# ZynqPL_DDR.net
KiCad netlist of a schematic drawn in Altium Designer
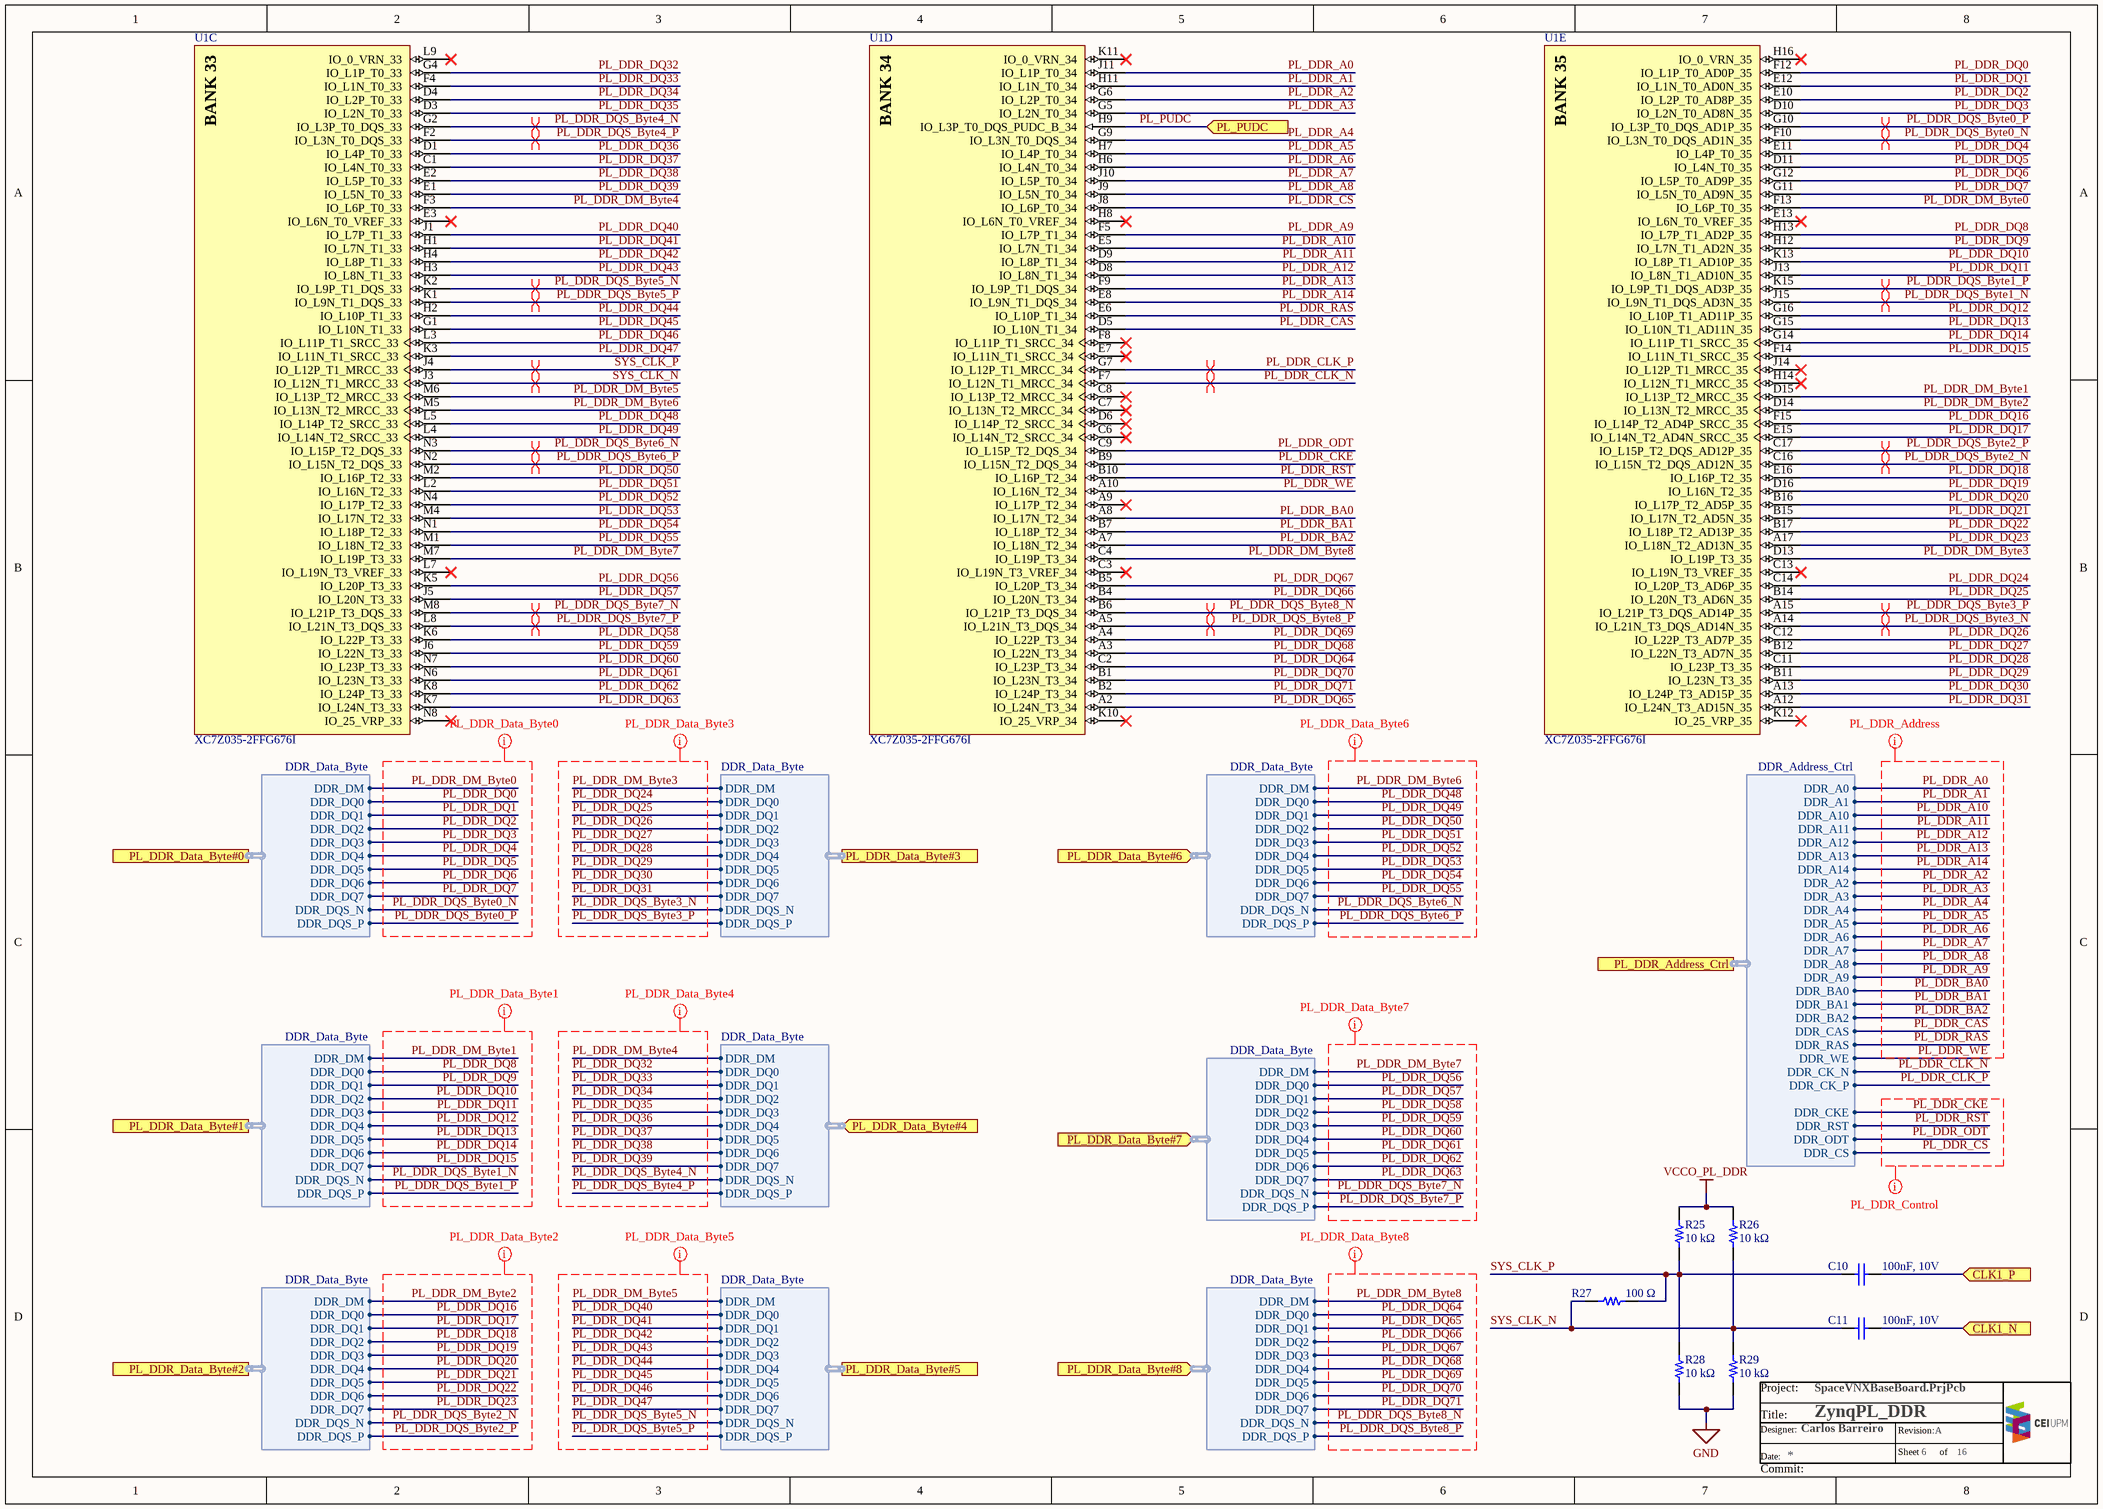
[diagram p0: ZynqPL_DDR.SchDoc]

(export (version "E")
  (design (tool "Eeschema 10.0.6"))
  (components
    (comp (ref "C10")
      (value "100nF, 10V")
      (footprint "WURTH_WCAP-CSGP_0402")
      (description "WCAP-CSGP Multilayer Ceramic Chip Capacitor, General Purpose, size 0402, X7R, 100nF, 10V")
      (fields
        (field (name "MANUFACTURER PART NUMBER") "885012205018")
        (field (name "MANUFACTURER") "Wurth Elektronik")
      )
      (libsource (lib "SpaceVNX") (part "885012205018"))
    )
    (comp (ref "C11")
      (value "100nF, 10V")
      (footprint "WURTH_WCAP-CSGP_0402")
      (description "WCAP-CSGP Multilayer Ceramic Chip Capacitor, General Purpose, size 0402, X7R, 100nF, 10V")
      (fields
        (field (name "MANUFACTURER PART NUMBER") "885012205018")
        (field (name "MANUFACTURER") "Wurth Elektronik")
      )
      (libsource (lib "SpaceVNX") (part "885012205018"))
    )
    (comp (ref "R25")
      (value "10 kΩ")
      (footprint "PANASONIC_ERJ2G_0402")
      (description "General Purpose Thick Film Chip Resistors")
      (fields (field (name "MANUFACTURER") "Panasonic"))
      (libsource (lib "SpaceVNX") (part "ERJ2RKF1002X"))
    )
    (comp (ref "R26")
      (value "10 kΩ")
      (footprint "PANASONIC_ERJ2G_0402")
      (description "General Purpose Thick Film Chip Resistors")
      (fields (field (name "MANUFACTURER") "Panasonic"))
      (libsource (lib "SpaceVNX") (part "ERJ2RKF1002X"))
    )
    (comp (ref "R27")
      (value "100 Ω")
      (footprint "PANASONIC_ERJ2G_0402")
      (description "General Purpose Thick Film Chip Resistors")
      (fields (field (name "MANUFACTURER") "Panasonic"))
      (libsource (lib "SpaceVNX") (part "ERJ2GEJ101X"))
    )
    (comp (ref "R28")
      (value "10 kΩ")
      (footprint "PANASONIC_ERJ2G_0402")
      (description "General Purpose Thick Film Chip Resistors")
      (fields (field (name "MANUFACTURER") "Panasonic"))
      (libsource (lib "SpaceVNX") (part "ERJ2RKF1002X"))
    )
    (comp (ref "R29")
      (value "10 kΩ")
      (footprint "PANASONIC_ERJ2G_0402")
      (description "General Purpose Thick Film Chip Resistors")
      (fields (field (name "MANUFACTURER") "Panasonic"))
      (libsource (lib "SpaceVNX") (part "ERJ2RKF1002X"))
    )
    (comp (ref "U1")
      (value "XC7Z035-2FFG676I")
      (footprint "XILINX_FBG676")
      (fields (field (name "PARTNUMBER") "XC7Z035-2FBG676I") (field (name "GENERIC PART NUMBER") "XC7Z035"))
      (libsource (lib "SpaceVNX") (part "XC7Z035-2FFG676I"))
    )
  )
  (nets
    (net (code "3") (name "/CLK1_N") (class "Default")
      (node (ref "C11") (pin "2") (pinfunction "2_2") (pintype "passive"))
    )
    (net (code "4") (name "/CLK1_P") (class "Default")
      (node (ref "C10") (pin "2") (pinfunction "2_2") (pintype "passive"))
    )
    (net (code "5") (name "/PL_DDR_A0") (class "Default")
      (node (ref "U1") (pin "J11") (pinfunction "IO_L1P_T0_34_J11") (pintype "bidirectional"))
    )
    (net (code "6") (name "/PL_DDR_A1") (class "Default")
      (node (ref "U1") (pin "H11") (pinfunction "IO_L1N_T0_34_H11") (pintype "bidirectional"))
    )
    (net (code "7") (name "/PL_DDR_A2") (class "Default")
      (node (ref "U1") (pin "G6") (pinfunction "IO_L2P_T0_34_G6") (pintype "bidirectional"))
    )
    (net (code "8") (name "/PL_DDR_A3") (class "Default")
      (node (ref "U1") (pin "G5") (pinfunction "IO_L2N_T0_34_G5") (pintype "bidirectional"))
    )
    (net (code "9") (name "/PL_DDR_A4") (class "Default")
      (node (ref "U1") (pin "G9") (pinfunction "IO_L3N_T0_DQS_34_G9") (pintype "bidirectional"))
    )
    (net (code "10") (name "/PL_DDR_A5") (class "Default")
      (node (ref "U1") (pin "H7") (pinfunction "IO_L4P_T0_34_H7") (pintype "bidirectional"))
    )
    (net (code "11") (name "/PL_DDR_A6") (class "Default")
      (node (ref "U1") (pin "H6") (pinfunction "IO_L4N_T0_34_H6") (pintype "bidirectional"))
    )
    (net (code "12") (name "/PL_DDR_A7") (class "Default")
      (node (ref "U1") (pin "J10") (pinfunction "IO_L5P_T0_34_J10") (pintype "bidirectional"))
    )
    (net (code "13") (name "/PL_DDR_A8") (class "Default")
      (node (ref "U1") (pin "J9") (pinfunction "IO_L5N_T0_34_J9") (pintype "bidirectional"))
    )
    (net (code "14") (name "/PL_DDR_A9") (class "Default")
      (node (ref "U1") (pin "F5") (pinfunction "IO_L7P_T1_34_F5") (pintype "bidirectional"))
    )
    (net (code "15") (name "/PL_DDR_A10") (class "Default")
      (node (ref "U1") (pin "E5") (pinfunction "IO_L7N_T1_34_E5") (pintype "bidirectional"))
    )
    (net (code "16") (name "/PL_DDR_A11") (class "Default")
      (node (ref "U1") (pin "D9") (pinfunction "IO_L8P_T1_34_D9") (pintype "bidirectional"))
    )
    (net (code "17") (name "/PL_DDR_A12") (class "Default")
      (node (ref "U1") (pin "D8") (pinfunction "IO_L8N_T1_34_D8") (pintype "bidirectional"))
    )
    (net (code "18") (name "/PL_DDR_A13") (class "Default")
      (node (ref "U1") (pin "F9") (pinfunction "IO_L9P_T1_DQS_34_F9") (pintype "bidirectional"))
    )
    (net (code "19") (name "/PL_DDR_A14") (class "Default")
      (node (ref "U1") (pin "E8") (pinfunction "IO_L9N_T1_DQS_34_E8") (pintype "bidirectional"))
    )
    (net (code "20") (name "/PL_DDR_BA0") (class "Default")
      (node (ref "U1") (pin "A8") (pinfunction "IO_L17N_T2_34_A8") (pintype "bidirectional"))
    )
    (net (code "21") (name "/PL_DDR_BA1") (class "Default")
      (node (ref "U1") (pin "B7") (pinfunction "IO_L18P_T2_34_B7") (pintype "bidirectional"))
    )
    (net (code "22") (name "/PL_DDR_BA2") (class "Default")
      (node (ref "U1") (pin "A7") (pinfunction "IO_L18N_T2_34_A7") (pintype "bidirectional"))
    )
    (net (code "23") (name "/PL_DDR_CAS") (class "Default")
      (node (ref "U1") (pin "D5") (pinfunction "IO_L10N_T1_34_D5") (pintype "bidirectional"))
    )
    (net (code "24") (name "/PL_DDR_CKE") (class "Default")
      (node (ref "U1") (pin "B9") (pinfunction "IO_L15N_T2_DQS_34_B9") (pintype "bidirectional"))
    )
    (net (code "25") (name "/PL_DDR_CLK_N") (class "Default")
      (node (ref "U1") (pin "F7") (pinfunction "IO_L12N_T1_MRCC_34_F7") (pintype "bidirectional"))
    )
    (net (code "26") (name "/PL_DDR_CLK_P") (class "Default")
      (node (ref "U1") (pin "G7") (pinfunction "IO_L12P_T1_MRCC_34_G7") (pintype "bidirectional"))
    )
    (net (code "27") (name "/PL_DDR_CS") (class "Default")
      (node (ref "U1") (pin "J8") (pinfunction "IO_L6P_T0_34_J8") (pintype "bidirectional"))
    )
    (net (code "28") (name "/PL_DDR_DM_Byte0") (class "Default")
      (node (ref "U1") (pin "F13") (pinfunction "IO_L6P_T0_35_F13") (pintype "bidirectional"))
    )
    (net (code "29") (name "/PL_DDR_DM_Byte1") (class "Default")
      (node (ref "U1") (pin "D15") (pinfunction "IO_L13P_T2_MRCC_35_D15") (pintype "bidirectional"))
    )
    (net (code "30") (name "/PL_DDR_DM_Byte2") (class "Default")
      (node (ref "U1") (pin "D14") (pinfunction "IO_L13N_T2_MRCC_35_D14") (pintype "bidirectional"))
    )
    (net (code "31") (name "/PL_DDR_DM_Byte3") (class "Default")
      (node (ref "U1") (pin "D13") (pinfunction "IO_L19P_T3_35_D13") (pintype "bidirectional"))
    )
    (net (code "32") (name "/PL_DDR_DM_Byte4") (class "Default")
      (node (ref "U1") (pin "F3") (pinfunction "IO_L6P_T0_33_F3") (pintype "bidirectional"))
    )
    (net (code "33") (name "/PL_DDR_DM_Byte5") (class "Default")
      (node (ref "U1") (pin "M6") (pinfunction "IO_L13P_T2_MRCC_33_M6") (pintype "bidirectional"))
    )
    (net (code "34") (name "/PL_DDR_DM_Byte6") (class "Default")
      (node (ref "U1") (pin "M5") (pinfunction "IO_L13N_T2_MRCC_33_M5") (pintype "bidirectional"))
    )
    (net (code "35") (name "/PL_DDR_DM_Byte7") (class "Default")
      (node (ref "U1") (pin "M7") (pinfunction "IO_L19P_T3_33_M7") (pintype "bidirectional"))
    )
    (net (code "36") (name "/PL_DDR_DM_Byte8") (class "Default")
      (node (ref "U1") (pin "C4") (pinfunction "IO_L19P_T3_34_C4") (pintype "bidirectional"))
    )
    (net (code "37") (name "/PL_DDR_DQ0") (class "Default")
      (node (ref "U1") (pin "F12") (pinfunction "IO_L1P_T0_AD0P_35_F12") (pintype "bidirectional"))
    )
    (net (code "38") (name "/PL_DDR_DQ1") (class "Default")
      (node (ref "U1") (pin "E12") (pinfunction "IO_L1N_T0_AD0N_35_E12") (pintype "bidirectional"))
    )
    (net (code "39") (name "/PL_DDR_DQ2") (class "Default")
      (node (ref "U1") (pin "E10") (pinfunction "IO_L2P_T0_AD8P_35_E10") (pintype "bidirectional"))
    )
    (net (code "40") (name "/PL_DDR_DQ3") (class "Default")
      (node (ref "U1") (pin "D10") (pinfunction "IO_L2N_T0_AD8N_35_D10") (pintype "bidirectional"))
    )
    (net (code "41") (name "/PL_DDR_DQ4") (class "Default")
      (node (ref "U1") (pin "E11") (pinfunction "IO_L4P_T0_35_E11") (pintype "bidirectional"))
    )
    (net (code "42") (name "/PL_DDR_DQ5") (class "Default")
      (node (ref "U1") (pin "D11") (pinfunction "IO_L4N_T0_35_D11") (pintype "bidirectional"))
    )
    (net (code "43") (name "/PL_DDR_DQ6") (class "Default")
      (node (ref "U1") (pin "G12") (pinfunction "IO_L5P_T0_AD9P_35_G12") (pintype "bidirectional"))
    )
    (net (code "44") (name "/PL_DDR_DQ7") (class "Default")
      (node (ref "U1") (pin "G11") (pinfunction "IO_L5N_T0_AD9N_35_G11") (pintype "bidirectional"))
    )
    (net (code "45") (name "/PL_DDR_DQ8") (class "Default")
      (node (ref "U1") (pin "H13") (pinfunction "IO_L7P_T1_AD2P_35_H13") (pintype "bidirectional"))
    )
    (net (code "46") (name "/PL_DDR_DQ9") (class "Default")
      (node (ref "U1") (pin "H12") (pinfunction "IO_L7N_T1_AD2N_35_H12") (pintype "bidirectional"))
    )
    (net (code "47") (name "/PL_DDR_DQ10") (class "Default")
      (node (ref "U1") (pin "K13") (pinfunction "IO_L8P_T1_AD10P_35_K13") (pintype "bidirectional"))
    )
    (net (code "48") (name "/PL_DDR_DQ11") (class "Default")
      (node (ref "U1") (pin "J13") (pinfunction "IO_L8N_T1_AD10N_35_J13") (pintype "bidirectional"))
    )
    (net (code "49") (name "/PL_DDR_DQ12") (class "Default")
      (node (ref "U1") (pin "G16") (pinfunction "IO_L10P_T1_AD11P_35_G16") (pintype "bidirectional"))
    )
    (net (code "50") (name "/PL_DDR_DQ13") (class "Default")
      (node (ref "U1") (pin "G15") (pinfunction "IO_L10N_T1_AD11N_35_G15") (pintype "bidirectional"))
    )
    (net (code "51") (name "/PL_DDR_DQ14") (class "Default")
      (node (ref "U1") (pin "G14") (pinfunction "IO_L11P_T1_SRCC_35_G14") (pintype "bidirectional"))
    )
    (net (code "52") (name "/PL_DDR_DQ15") (class "Default")
      (node (ref "U1") (pin "F14") (pinfunction "IO_L11N_T1_SRCC_35_F14") (pintype "bidirectional"))
    )
    (net (code "53") (name "/PL_DDR_DQ16") (class "Default")
      (node (ref "U1") (pin "F15") (pinfunction "IO_L14P_T2_AD4P_SRCC_35_F15") (pintype "bidirectional"))
    )
    (net (code "54") (name "/PL_DDR_DQ17") (class "Default")
      (node (ref "U1") (pin "E15") (pinfunction "IO_L14N_T2_AD4N_SRCC_35_E15") (pintype "bidirectional"))
    )
    (net (code "55") (name "/PL_DDR_DQ18") (class "Default")
      (node (ref "U1") (pin "E16") (pinfunction "IO_L16P_T2_35_E16") (pintype "bidirectional"))
    )
    (net (code "56") (name "/PL_DDR_DQ19") (class "Default")
      (node (ref "U1") (pin "D16") (pinfunction "IO_L16N_T2_35_D16") (pintype "bidirectional"))
    )
    (net (code "57") (name "/PL_DDR_DQ20") (class "Default")
      (node (ref "U1") (pin "B16") (pinfunction "IO_L17P_T2_AD5P_35_B16") (pintype "bidirectional"))
    )
    (net (code "58") (name "/PL_DDR_DQ21") (class "Default")
      (node (ref "U1") (pin "B15") (pinfunction "IO_L17N_T2_AD5N_35_B15") (pintype "bidirectional"))
    )
    (net (code "59") (name "/PL_DDR_DQ22") (class "Default")
      (node (ref "U1") (pin "B17") (pinfunction "IO_L18P_T2_AD13P_35_B17") (pintype "bidirectional"))
    )
    (net (code "60") (name "/PL_DDR_DQ23") (class "Default")
      (node (ref "U1") (pin "A17") (pinfunction "IO_L18N_T2_AD13N_35_A17") (pintype "bidirectional"))
    )
    (net (code "61") (name "/PL_DDR_DQ24") (class "Default")
      (node (ref "U1") (pin "C14") (pinfunction "IO_L20P_T3_AD6P_35_C14") (pintype "bidirectional"))
    )
    (net (code "62") (name "/PL_DDR_DQ25") (class "Default")
      (node (ref "U1") (pin "B14") (pinfunction "IO_L20N_T3_AD6N_35_B14") (pintype "bidirectional"))
    )
    (net (code "63") (name "/PL_DDR_DQ26") (class "Default")
      (node (ref "U1") (pin "C12") (pinfunction "IO_L22P_T3_AD7P_35_C12") (pintype "bidirectional"))
    )
    (net (code "64") (name "/PL_DDR_DQ27") (class "Default")
      (node (ref "U1") (pin "B12") (pinfunction "IO_L22N_T3_AD7N_35_B12") (pintype "bidirectional"))
    )
    (net (code "65") (name "/PL_DDR_DQ28") (class "Default")
      (node (ref "U1") (pin "C11") (pinfunction "IO_L23P_T3_35_C11") (pintype "bidirectional"))
    )
    (net (code "66") (name "/PL_DDR_DQ29") (class "Default")
      (node (ref "U1") (pin "B11") (pinfunction "IO_L23N_T3_35_B11") (pintype "bidirectional"))
    )
    (net (code "67") (name "/PL_DDR_DQ30") (class "Default")
      (node (ref "U1") (pin "A13") (pinfunction "IO_L24P_T3_AD15P_35_A13") (pintype "bidirectional"))
    )
    (net (code "68") (name "/PL_DDR_DQ31") (class "Default")
      (node (ref "U1") (pin "A12") (pinfunction "IO_L24N_T3_AD15N_35_A12") (pintype "bidirectional"))
    )
    (net (code "69") (name "/PL_DDR_DQ32") (class "Default")
      (node (ref "U1") (pin "G4") (pinfunction "IO_L1P_T0_33_G4") (pintype "bidirectional"))
    )
    (net (code "70") (name "/PL_DDR_DQ33") (class "Default")
      (node (ref "U1") (pin "F4") (pinfunction "IO_L1N_T0_33_F4") (pintype "bidirectional"))
    )
    (net (code "71") (name "/PL_DDR_DQ34") (class "Default")
      (node (ref "U1") (pin "D4") (pinfunction "IO_L2P_T0_33_D4") (pintype "bidirectional"))
    )
    (net (code "72") (name "/PL_DDR_DQ35") (class "Default")
      (node (ref "U1") (pin "D3") (pinfunction "IO_L2N_T0_33_D3") (pintype "bidirectional"))
    )
    (net (code "73") (name "/PL_DDR_DQ36") (class "Default")
      (node (ref "U1") (pin "D1") (pinfunction "IO_L4P_T0_33_D1") (pintype "bidirectional"))
    )
    (net (code "74") (name "/PL_DDR_DQ37") (class "Default")
      (node (ref "U1") (pin "C1") (pinfunction "IO_L4N_T0_33_C1") (pintype "bidirectional"))
    )
    (net (code "75") (name "/PL_DDR_DQ38") (class "Default")
      (node (ref "U1") (pin "E2") (pinfunction "IO_L5P_T0_33_E2") (pintype "bidirectional"))
    )
    (net (code "76") (name "/PL_DDR_DQ39") (class "Default")
      (node (ref "U1") (pin "E1") (pinfunction "IO_L5N_T0_33_E1") (pintype "bidirectional"))
    )
    (net (code "77") (name "/PL_DDR_DQ40") (class "Default")
      (node (ref "U1") (pin "J1") (pinfunction "IO_L7P_T1_33_J1") (pintype "bidirectional"))
    )
    (net (code "78") (name "/PL_DDR_DQ41") (class "Default")
      (node (ref "U1") (pin "H1") (pinfunction "IO_L7N_T1_33_H1") (pintype "bidirectional"))
    )
    (net (code "79") (name "/PL_DDR_DQ42") (class "Default")
      (node (ref "U1") (pin "H4") (pinfunction "IO_L8P_T1_33_H4") (pintype "bidirectional"))
    )
    (net (code "80") (name "/PL_DDR_DQ43") (class "Default")
      (node (ref "U1") (pin "H3") (pinfunction "IO_L8N_T1_33_H3") (pintype "bidirectional"))
    )
    (net (code "81") (name "/PL_DDR_DQ44") (class "Default")
      (node (ref "U1") (pin "H2") (pinfunction "IO_L10P_T1_33_H2") (pintype "bidirectional"))
    )
    (net (code "82") (name "/PL_DDR_DQ45") (class "Default")
      (node (ref "U1") (pin "G1") (pinfunction "IO_L10N_T1_33_G1") (pintype "bidirectional"))
    )
    (net (code "83") (name "/PL_DDR_DQ46") (class "Default")
      (node (ref "U1") (pin "L3") (pinfunction "IO_L11P_T1_SRCC_33_L3") (pintype "bidirectional"))
    )
    (net (code "84") (name "/PL_DDR_DQ47") (class "Default")
      (node (ref "U1") (pin "K3") (pinfunction "IO_L11N_T1_SRCC_33_K3") (pintype "bidirectional"))
    )
    (net (code "85") (name "/PL_DDR_DQ48") (class "Default")
      (node (ref "U1") (pin "L5") (pinfunction "IO_L14P_T2_SRCC_33_L5") (pintype "bidirectional"))
    )
    (net (code "86") (name "/PL_DDR_DQ49") (class "Default")
      (node (ref "U1") (pin "L4") (pinfunction "IO_L14N_T2_SRCC_33_L4") (pintype "bidirectional"))
    )
    (net (code "87") (name "/PL_DDR_DQ50") (class "Default")
      (node (ref "U1") (pin "M2") (pinfunction "IO_L16P_T2_33_M2") (pintype "bidirectional"))
    )
    (net (code "88") (name "/PL_DDR_DQ51") (class "Default")
      (node (ref "U1") (pin "L2") (pinfunction "IO_L16N_T2_33_L2") (pintype "bidirectional"))
    )
    (net (code "89") (name "/PL_DDR_DQ52") (class "Default")
      (node (ref "U1") (pin "N4") (pinfunction "IO_L17P_T2_33_N4") (pintype "bidirectional"))
    )
    (net (code "90") (name "/PL_DDR_DQ53") (class "Default")
      (node (ref "U1") (pin "M4") (pinfunction "IO_L17N_T2_33_M4") (pintype "bidirectional"))
    )
    (net (code "91") (name "/PL_DDR_DQ54") (class "Default")
      (node (ref "U1") (pin "N1") (pinfunction "IO_L18P_T2_33_N1") (pintype "bidirectional"))
    )
    (net (code "92") (name "/PL_DDR_DQ55") (class "Default")
      (node (ref "U1") (pin "M1") (pinfunction "IO_L18N_T2_33_M1") (pintype "bidirectional"))
    )
    (net (code "93") (name "/PL_DDR_DQ56") (class "Default")
      (node (ref "U1") (pin "K5") (pinfunction "IO_L20P_T3_33_K5") (pintype "bidirectional"))
    )
    (net (code "94") (name "/PL_DDR_DQ57") (class "Default")
      (node (ref "U1") (pin "J5") (pinfunction "IO_L20N_T3_33_J5") (pintype "bidirectional"))
    )
    (net (code "95") (name "/PL_DDR_DQ58") (class "Default")
      (node (ref "U1") (pin "K6") (pinfunction "IO_L22P_T3_33_K6") (pintype "bidirectional"))
    )
    (net (code "96") (name "/PL_DDR_DQ59") (class "Default")
      (node (ref "U1") (pin "J6") (pinfunction "IO_L22N_T3_33_J6") (pintype "bidirectional"))
    )
    (net (code "97") (name "/PL_DDR_DQ60") (class "Default")
      (node (ref "U1") (pin "N7") (pinfunction "IO_L23P_T3_33_N7") (pintype "bidirectional"))
    )
    (net (code "98") (name "/PL_DDR_DQ61") (class "Default")
      (node (ref "U1") (pin "N6") (pinfunction "IO_L23N_T3_33_N6") (pintype "bidirectional"))
    )
    (net (code "99") (name "/PL_DDR_DQ62") (class "Default")
      (node (ref "U1") (pin "K8") (pinfunction "IO_L24P_T3_33_K8") (pintype "bidirectional"))
    )
    (net (code "100") (name "/PL_DDR_DQ63") (class "Default")
      (node (ref "U1") (pin "K7") (pinfunction "IO_L24N_T3_33_K7") (pintype "bidirectional"))
    )
    (net (code "101") (name "/PL_DDR_DQ64") (class "Default")
      (node (ref "U1") (pin "C2") (pinfunction "IO_L23P_T3_34_C2") (pintype "bidirectional"))
    )
    (net (code "102") (name "/PL_DDR_DQ65") (class "Default")
      (node (ref "U1") (pin "A2") (pinfunction "IO_L24N_T3_34_A2") (pintype "bidirectional"))
    )
    (net (code "103") (name "/PL_DDR_DQ66") (class "Default")
      (node (ref "U1") (pin "B4") (pinfunction "IO_L20N_T3_34_B4") (pintype "bidirectional"))
    )
    (net (code "104") (name "/PL_DDR_DQ67") (class "Default")
      (node (ref "U1") (pin "B5") (pinfunction "IO_L20P_T3_34_B5") (pintype "bidirectional"))
    )
    (net (code "105") (name "/PL_DDR_DQ68") (class "Default")
      (node (ref "U1") (pin "A3") (pinfunction "IO_L22N_T3_34_A3") (pintype "bidirectional"))
    )
    (net (code "106") (name "/PL_DDR_DQ69") (class "Default")
      (node (ref "U1") (pin "A4") (pinfunction "IO_L22P_T3_34_A4") (pintype "bidirectional"))
    )
    (net (code "107") (name "/PL_DDR_DQ70") (class "Default")
      (node (ref "U1") (pin "B1") (pinfunction "IO_L23N_T3_34_B1") (pintype "bidirectional"))
    )
    (net (code "108") (name "/PL_DDR_DQ71") (class "Default")
      (node (ref "U1") (pin "B2") (pinfunction "IO_L24P_T3_34_B2") (pintype "bidirectional"))
    )
    (net (code "109") (name "/PL_DDR_DQS_Byte0_N") (class "Default")
      (node (ref "U1") (pin "F10") (pinfunction "IO_L3N_T0_DQS_AD1N_35_F10") (pintype "bidirectional"))
    )
    (net (code "110") (name "/PL_DDR_DQS_Byte0_P") (class "Default")
      (node (ref "U1") (pin "G10") (pinfunction "IO_L3P_T0_DQS_AD1P_35_G10") (pintype "bidirectional"))
    )
    (net (code "111") (name "/PL_DDR_DQS_Byte1_N") (class "Default")
      (node (ref "U1") (pin "J15") (pinfunction "IO_L9N_T1_DQS_AD3N_35_J15") (pintype "bidirectional"))
    )
    (net (code "112") (name "/PL_DDR_DQS_Byte1_P") (class "Default")
      (node (ref "U1") (pin "K15") (pinfunction "IO_L9P_T1_DQS_AD3P_35_K15") (pintype "bidirectional"))
    )
    (net (code "113") (name "/PL_DDR_DQS_Byte2_N") (class "Default")
      (node (ref "U1") (pin "C16") (pinfunction "IO_L15N_T2_DQS_AD12N_35_C16") (pintype "bidirectional"))
    )
    (net (code "114") (name "/PL_DDR_DQS_Byte2_P") (class "Default")
      (node (ref "U1") (pin "C17") (pinfunction "IO_L15P_T2_DQS_AD12P_35_C17") (pintype "bidirectional"))
    )
    (net (code "115") (name "/PL_DDR_DQS_Byte3_N") (class "Default")
      (node (ref "U1") (pin "A14") (pinfunction "IO_L21N_T3_DQS_AD14N_35_A14") (pintype "bidirectional"))
    )
    (net (code "116") (name "/PL_DDR_DQS_Byte3_P") (class "Default")
      (node (ref "U1") (pin "A15") (pinfunction "IO_L21P_T3_DQS_AD14P_35_A15") (pintype "bidirectional"))
    )
    (net (code "117") (name "/PL_DDR_DQS_Byte4_N") (class "Default")
      (node (ref "U1") (pin "G2") (pinfunction "IO_L3P_T0_DQS_33_G2") (pintype "bidirectional"))
    )
    (net (code "118") (name "/PL_DDR_DQS_Byte4_P") (class "Default")
      (node (ref "U1") (pin "F2") (pinfunction "IO_L3N_T0_DQS_33_F2") (pintype "bidirectional"))
    )
    (net (code "119") (name "/PL_DDR_DQS_Byte5_N") (class "Default")
      (node (ref "U1") (pin "K2") (pinfunction "IO_L9P_T1_DQS_33_K2") (pintype "bidirectional"))
    )
    (net (code "120") (name "/PL_DDR_DQS_Byte5_P") (class "Default")
      (node (ref "U1") (pin "K1") (pinfunction "IO_L9N_T1_DQS_33_K1") (pintype "bidirectional"))
    )
    (net (code "121") (name "/PL_DDR_DQS_Byte6_N") (class "Default")
      (node (ref "U1") (pin "N3") (pinfunction "IO_L15P_T2_DQS_33_N3") (pintype "bidirectional"))
    )
    (net (code "122") (name "/PL_DDR_DQS_Byte6_P") (class "Default")
      (node (ref "U1") (pin "N2") (pinfunction "IO_L15N_T2_DQS_33_N2") (pintype "bidirectional"))
    )
    (net (code "123") (name "/PL_DDR_DQS_Byte7_N") (class "Default")
      (node (ref "U1") (pin "M8") (pinfunction "IO_L21P_T3_DQS_33_M8") (pintype "bidirectional"))
    )
    (net (code "124") (name "/PL_DDR_DQS_Byte7_P") (class "Default")
      (node (ref "U1") (pin "L8") (pinfunction "IO_L21N_T3_DQS_33_L8") (pintype "bidirectional"))
    )
    (net (code "125") (name "/PL_DDR_DQS_Byte8_N") (class "Default")
      (node (ref "U1") (pin "B6") (pinfunction "IO_L21P_T3_DQS_34_B6") (pintype "bidirectional"))
    )
    (net (code "126") (name "/PL_DDR_DQS_Byte8_P") (class "Default")
      (node (ref "U1") (pin "A5") (pinfunction "IO_L21N_T3_DQS_34_A5") (pintype "bidirectional"))
    )
    (net (code "127") (name "/PL_DDR_ODT") (class "Default")
      (node (ref "U1") (pin "C9") (pinfunction "IO_L15P_T2_DQS_34_C9") (pintype "bidirectional"))
    )
    (net (code "128") (name "/PL_DDR_RAS") (class "Default")
      (node (ref "U1") (pin "E6") (pinfunction "IO_L10P_T1_34_E6") (pintype "bidirectional"))
    )
    (net (code "129") (name "/PL_DDR_RST") (class "Default")
      (node (ref "U1") (pin "B10") (pinfunction "IO_L16P_T2_34_B10") (pintype "bidirectional"))
    )
    (net (code "130") (name "/PL_DDR_WE") (class "Default")
      (node (ref "U1") (pin "A10") (pinfunction "IO_L16N_T2_34_A10") (pintype "bidirectional"))
    )
    (net (code "131") (name "/PL_PUDC") (class "Default")
      (node (ref "U1") (pin "H9") (pinfunction "IO_L3P_T0_DQS_PUDC_B_34_H9") (pintype "bidirectional"))
    )
    (net (code "132") (name "/SYS_CLK_N") (class "Default")
      (node (ref "C11") (pin "1") (pinfunction "1_1") (pintype "passive"))
      (node (ref "R26") (pin "1") (pinfunction "1_1") (pintype "passive"))
      (node (ref "R27") (pin "1") (pinfunction "1_1") (pintype "passive"))
      (node (ref "R29") (pin "2") (pinfunction "2_2") (pintype "passive"))
      (node (ref "U1") (pin "J3") (pinfunction "IO_L12N_T1_MRCC_33_J3") (pintype "bidirectional"))
    )
    (net (code "133") (name "/SYS_CLK_P") (class "Default")
      (node (ref "C10") (pin "1") (pinfunction "1_1") (pintype "passive"))
      (node (ref "R25") (pin "1") (pinfunction "1_1") (pintype "passive"))
      (node (ref "R27") (pin "2") (pinfunction "2_2") (pintype "passive"))
      (node (ref "R28") (pin "2") (pinfunction "2_2") (pintype "passive"))
      (node (ref "U1") (pin "J4") (pinfunction "IO_L12P_T1_MRCC_33_J4") (pintype "bidirectional"))
    )
    (net (code "136") (name "GND") (class "Default")
      (node (ref "R28") (pin "1") (pinfunction "1_1") (pintype "passive"))
      (node (ref "R29") (pin "1") (pinfunction "1_1") (pintype "passive"))
    )
    (net (code "137") (name "VCCO_PL_DDR") (class "Default")
      (node (ref "R25") (pin "2") (pinfunction "2_2") (pintype "passive"))
      (node (ref "R26") (pin "2") (pinfunction "2_2") (pintype "passive"))
    )
    (net (code "138") (name "unconnected-(U1C-IO_0_VRN_33-PadL9)") (class "Default")
      (node (ref "U1") (pin "L9") (pinfunction "IO_0_VRN_33_L9") (pintype "bidirectional+no_connect"))
    )
    (net (code "139") (name "unconnected-(U1C-IO_25_VRP_33-PadN8)") (class "Default")
      (node (ref "U1") (pin "N8") (pinfunction "IO_25_VRP_33_N8") (pintype "bidirectional+no_connect"))
    )
    (net (code "140") (name "unconnected-(U1C-IO_L6N_T0_VREF_33-PadE3)") (class "Default")
      (node (ref "U1") (pin "E3") (pinfunction "IO_L6N_T0_VREF_33_E3") (pintype "bidirectional+no_connect"))
    )
    (net (code "141") (name "unconnected-(U1C-IO_L19N_T3_VREF_33-PadL7)") (class "Default")
      (node (ref "U1") (pin "L7") (pinfunction "IO_L19N_T3_VREF_33_L7") (pintype "bidirectional+no_connect"))
    )
    (net (code "142") (name "unconnected-(U1D-IO_0_VRN_34-PadK11)") (class "Default")
      (node (ref "U1") (pin "K11") (pinfunction "IO_0_VRN_34_K11") (pintype "bidirectional+no_connect"))
    )
    (net (code "143") (name "unconnected-(U1D-IO_25_VRP_34-PadK10)") (class "Default")
      (node (ref "U1") (pin "K10") (pinfunction "IO_25_VRP_34_K10") (pintype "bidirectional+no_connect"))
    )
    (net (code "144") (name "unconnected-(U1D-IO_L6N_T0_VREF_34-PadH8)") (class "Default")
      (node (ref "U1") (pin "H8") (pinfunction "IO_L6N_T0_VREF_34_H8") (pintype "bidirectional+no_connect"))
    )
    (net (code "145") (name "unconnected-(U1D-IO_L11N_T1_SRCC_34-PadE7)") (class "Default")
      (node (ref "U1") (pin "E7") (pinfunction "IO_L11N_T1_SRCC_34_E7") (pintype "bidirectional+no_connect"))
    )
    (net (code "146") (name "unconnected-(U1D-IO_L11P_T1_SRCC_34-PadF8)") (class "Default")
      (node (ref "U1") (pin "F8") (pinfunction "IO_L11P_T1_SRCC_34_F8") (pintype "bidirectional+no_connect"))
    )
    (net (code "147") (name "unconnected-(U1D-IO_L13N_T2_MRCC_34-PadC7)") (class "Default")
      (node (ref "U1") (pin "C7") (pinfunction "IO_L13N_T2_MRCC_34_C7") (pintype "bidirectional+no_connect"))
    )
    (net (code "148") (name "unconnected-(U1D-IO_L13P_T2_MRCC_34-PadC8)") (class "Default")
      (node (ref "U1") (pin "C8") (pinfunction "IO_L13P_T2_MRCC_34_C8") (pintype "bidirectional+no_connect"))
    )
    (net (code "149") (name "unconnected-(U1D-IO_L14N_T2_SRCC_34-PadC6)") (class "Default")
      (node (ref "U1") (pin "C6") (pinfunction "IO_L14N_T2_SRCC_34_C6") (pintype "bidirectional+no_connect"))
    )
    (net (code "150") (name "unconnected-(U1D-IO_L14P_T2_SRCC_34-PadD6)") (class "Default")
      (node (ref "U1") (pin "D6") (pinfunction "IO_L14P_T2_SRCC_34_D6") (pintype "bidirectional+no_connect"))
    )
    (net (code "151") (name "unconnected-(U1D-IO_L17P_T2_34-PadA9)") (class "Default")
      (node (ref "U1") (pin "A9") (pinfunction "IO_L17P_T2_34_A9") (pintype "bidirectional+no_connect"))
    )
    (net (code "152") (name "unconnected-(U1D-IO_L19N_T3_VREF_34-PadC3)") (class "Default")
      (node (ref "U1") (pin "C3") (pinfunction "IO_L19N_T3_VREF_34_C3") (pintype "bidirectional+no_connect"))
    )
    (net (code "153") (name "unconnected-(U1E-IO_0_VRN_35-PadH16)") (class "Default")
      (node (ref "U1") (pin "H16") (pinfunction "IO_0_VRN_35_H16") (pintype "bidirectional+no_connect"))
    )
    (net (code "154") (name "unconnected-(U1E-IO_25_VRP_35-PadK12)") (class "Default")
      (node (ref "U1") (pin "K12") (pinfunction "IO_25_VRP_35_K12") (pintype "bidirectional+no_connect"))
    )
    (net (code "155") (name "unconnected-(U1E-IO_L6N_T0_VREF_35-PadE13)") (class "Default")
      (node (ref "U1") (pin "E13") (pinfunction "IO_L6N_T0_VREF_35_E13") (pintype "bidirectional+no_connect"))
    )
    (net (code "156") (name "unconnected-(U1E-IO_L12N_T1_MRCC_35-PadH14)") (class "Default")
      (node (ref "U1") (pin "H14") (pinfunction "IO_L12N_T1_MRCC_35_H14") (pintype "bidirectional+no_connect"))
    )
    (net (code "157") (name "unconnected-(U1E-IO_L12P_T1_MRCC_35-PadJ14)") (class "Default")
      (node (ref "U1") (pin "J14") (pinfunction "IO_L12P_T1_MRCC_35_J14") (pintype "bidirectional+no_connect"))
    )
    (net (code "158") (name "unconnected-(U1E-IO_L19N_T3_VREF_35-PadC13)") (class "Default")
      (node (ref "U1") (pin "C13") (pinfunction "IO_L19N_T3_VREF_35_C13") (pintype "bidirectional+no_connect"))
    )
  )
)
